# POWER.net
KiCad netlist of a schematic drawn in Altium Designer
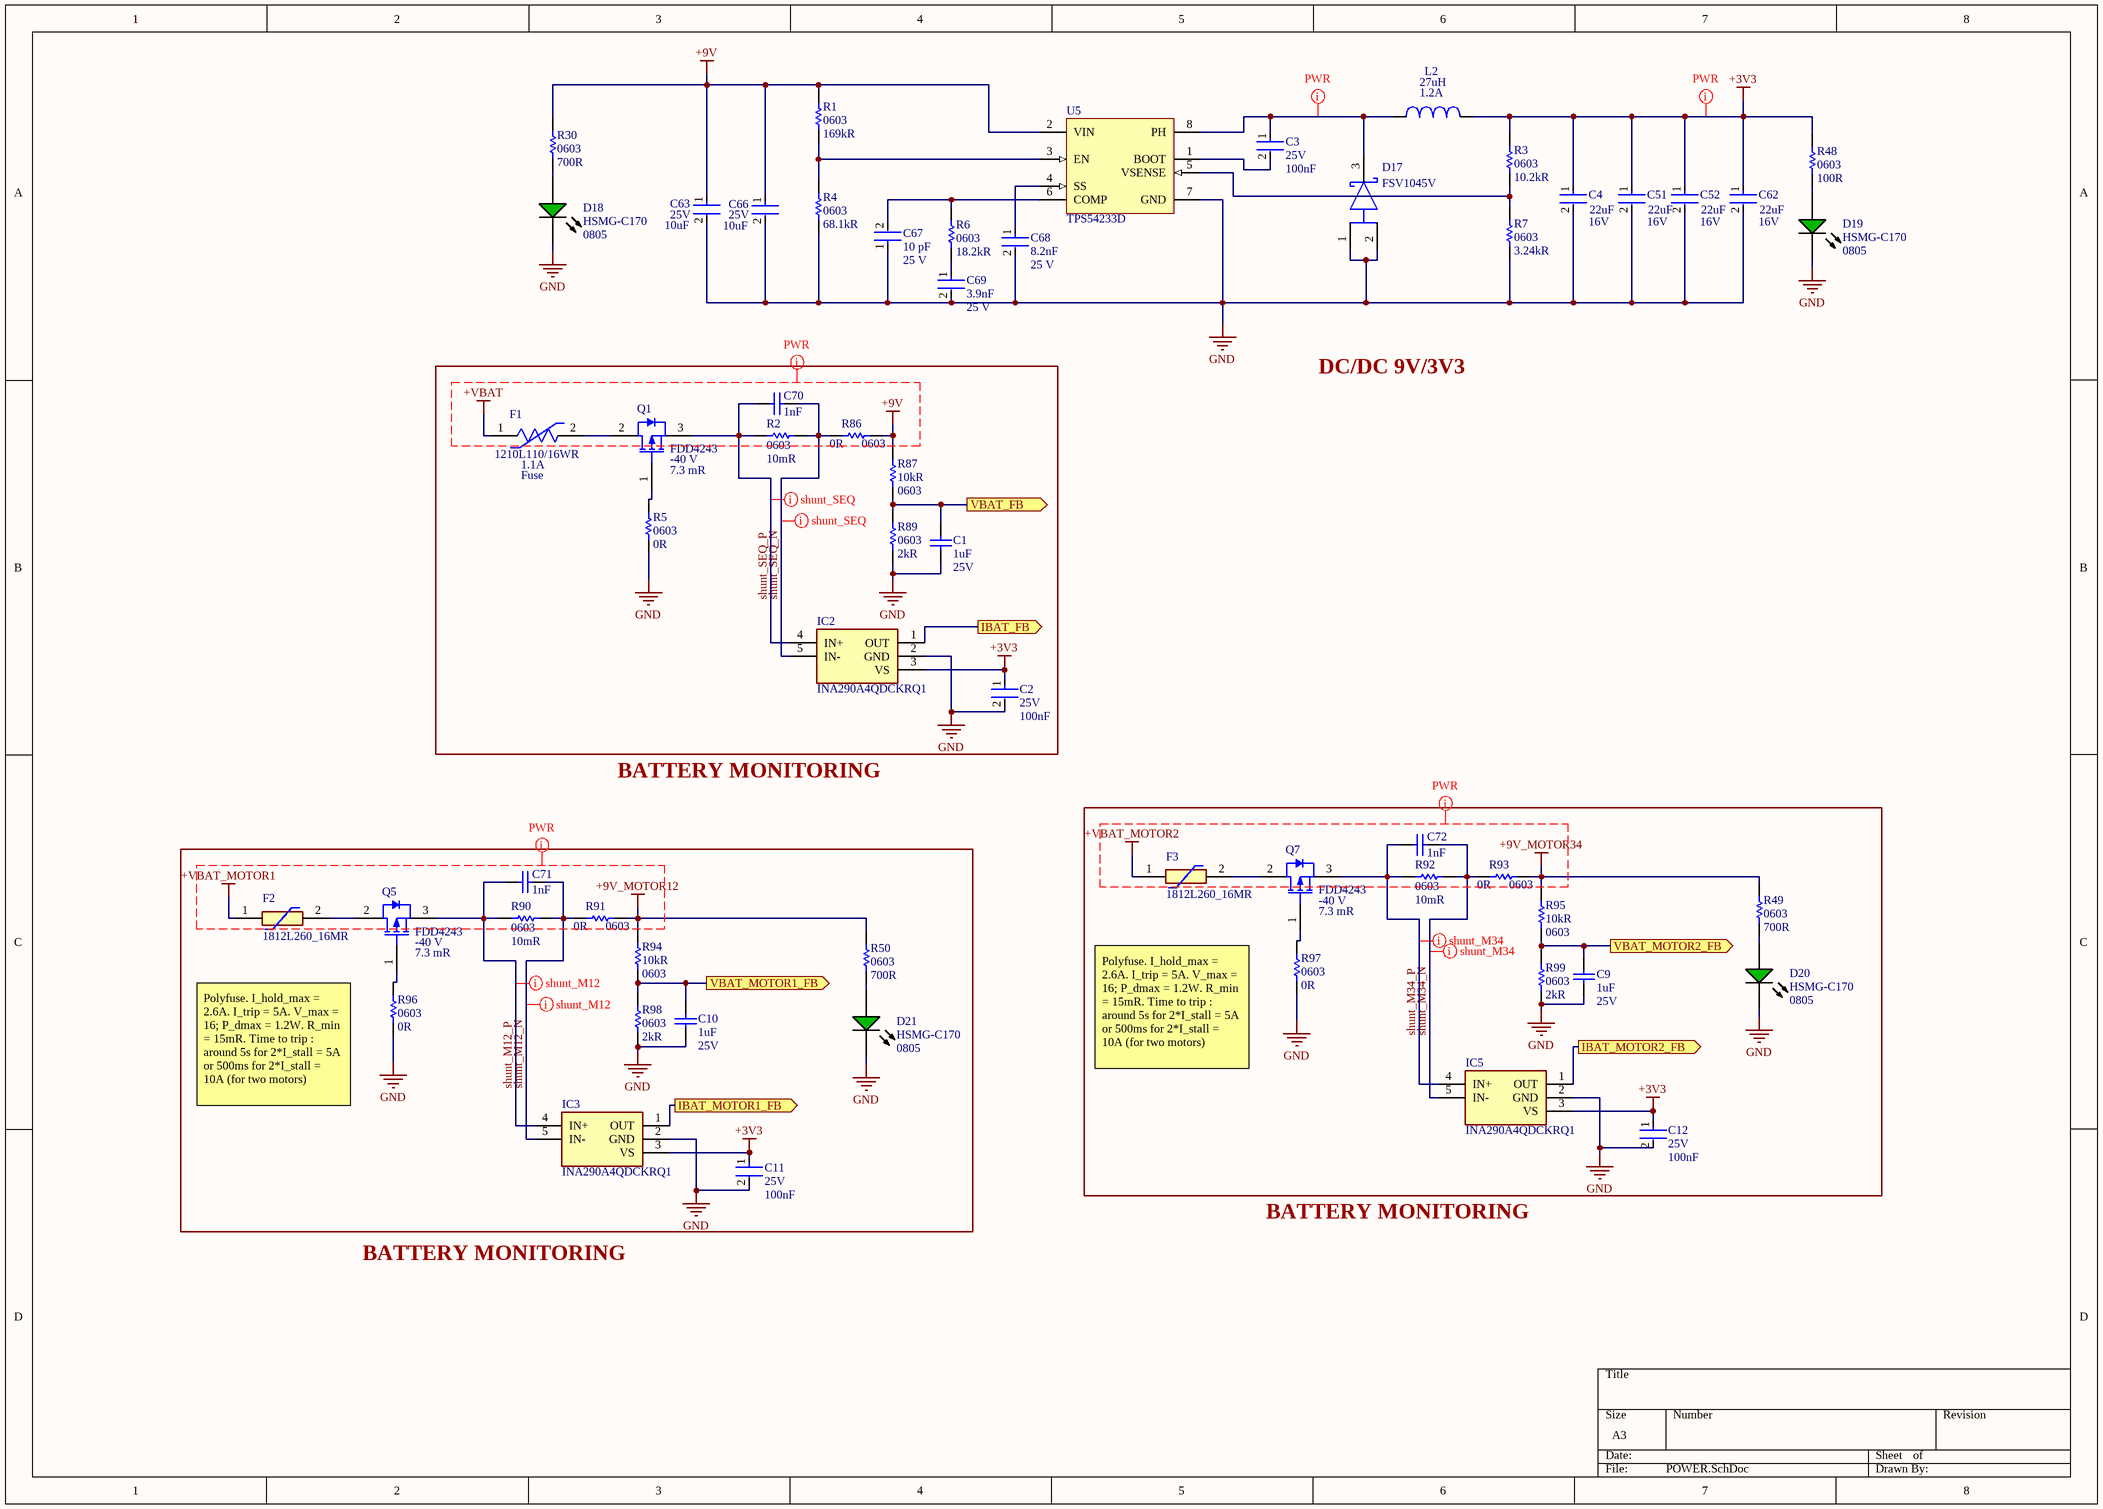
[diagram p0: POWER.SchDoc]

(export (version "E")
  (design (tool "Eeschema 10.0.6"))
  (components
    (comp (ref "C1")
      (value "C0603C105K3PAC7867")
      (footprint "CAPC1608X90X35LL15T15")
      (fields
        (field (name "MANUFACTURER") "Kemet")
        (field (name "MANUFACTURER PART NUMBER") "C0603C105K3PACTU")
        (field (name "CAPACITANCE") "1uF")
        (field (name "TOLERANCE") "10%")
        (field (name "VOLTAGE RATING (DC)") "25V")
      )
      (libsource (lib "Altium Content Vault") (part "CAP"))
    )
    (comp (ref "C2")
      (value "CGA3E2X7R1E104K080AA")
      (footprint "FP-CGA3E-0_3-0_1-MFG")
      (description "Cap Ceramic 100nF 25V X7R 10% Pad SMD 0603 +125°C Automotive T/R")
      (fields
        (field (name "VOLTAGE RATING (DC)") "25V")
        (field (name "CAPACITANCE") "100nF")
        (field (name "TOLERANCE") "10%")
        (field (name "MANUFACTURER") "TDK")
      )
      (libsource (lib "Altium Content Vault") (part "b4654b650e69147ec39a6b967a45e02"))
    )
    (comp (ref "C3")
      (value "CGA3E2X7R1E104K080AA")
      (footprint "FP-CGA3E-0_3-0_1-MFG")
      (description "Cap Ceramic 100nF 25V X7R 10% Pad SMD 0603 +125°C Automotive T/R")
      (fields
        (field (name "VOLTAGE RATING (DC)") "25V")
        (field (name "CAPACITANCE") "100nF")
        (field (name "TOLERANCE") "10%")
        (field (name "MANUFACTURER") "TDK")
      )
      (libsource (lib "Altium Content Vault") (part "b4654b650e69147ec39a6b967a45e02"))
    )
    (comp (ref "C4")
      (value "22uF")
      (footprint "FP-C2012-125-MFG")
      (description "CAP CER 22UF 16V X5R 0805")
      (fields
        (field (name "MANUFACTURER") "TDK")
        (field (name "OCTOPART") "https://octopart.com/c2012x5r1c226k125ac-tdk-25947713")
        (field (name "VOLTAGE") "16V")
      )
      (libsource (lib "Altium Content Vault") (part "11868f565c42a9108669ba33697ecf6"))
    )
    (comp (ref "C9")
      (value "C0603C105K3PAC7867")
      (footprint "CAPC1608X90X35LL15T15")
      (fields
        (field (name "MANUFACTURER") "Kemet")
        (field (name "MANUFACTURER PART NUMBER") "C0603C105K3PACTU")
        (field (name "CAPACITANCE") "1uF")
        (field (name "TOLERANCE") "10%")
        (field (name "VOLTAGE RATING (DC)") "25V")
      )
      (libsource (lib "Altium Content Vault") (part "CAP"))
    )
    (comp (ref "C10")
      (value "C0603C105K3PAC7867")
      (footprint "CAPC1608X90X35LL15T15")
      (fields
        (field (name "MANUFACTURER") "Kemet")
        (field (name "MANUFACTURER PART NUMBER") "C0603C105K3PACTU")
        (field (name "CAPACITANCE") "1uF")
        (field (name "TOLERANCE") "10%")
        (field (name "VOLTAGE RATING (DC)") "25V")
      )
      (libsource (lib "Altium Content Vault") (part "CAP"))
    )
    (comp (ref "C11")
      (value "CGA3E2X7R1E104K080AA")
      (footprint "FP-CGA3E-0_3-0_1-MFG")
      (description "Cap Ceramic 100nF 25V X7R 10% Pad SMD 0603 +125°C Automotive T/R")
      (fields
        (field (name "VOLTAGE RATING (DC)") "25V")
        (field (name "CAPACITANCE") "100nF")
        (field (name "TOLERANCE") "10%")
        (field (name "MANUFACTURER") "TDK")
      )
      (libsource (lib "Altium Content Vault") (part "b4654b650e69147ec39a6b967a45e02"))
    )
    (comp (ref "C12")
      (value "CGA3E2X7R1E104K080AA")
      (footprint "FP-CGA3E-0_3-0_1-MFG")
      (description "Cap Ceramic 100nF 25V X7R 10% Pad SMD 0603 +125°C Automotive T/R")
      (fields
        (field (name "VOLTAGE RATING (DC)") "25V")
        (field (name "CAPACITANCE") "100nF")
        (field (name "TOLERANCE") "10%")
        (field (name "MANUFACTURER") "TDK")
      )
      (libsource (lib "Altium Content Vault") (part "b4654b650e69147ec39a6b967a45e02"))
    )
    (comp (ref "C51")
      (value "22uF")
      (footprint "FP-C2012-125-MFG")
      (description "CAP CER 22UF 16V X5R 0805")
      (fields
        (field (name "MANUFACTURER") "TDK")
        (field (name "OCTOPART") "https://octopart.com/c2012x5r1c226k125ac-tdk-25947713")
        (field (name "VOLTAGE") "16V")
      )
      (libsource (lib "Altium Content Vault") (part "11868f565c42a9108669ba33697ecf6"))
    )
    (comp (ref "C52")
      (value "22uF")
      (footprint "FP-C2012-125-MFG")
      (description "CAP CER 22UF 16V X5R 0805")
      (fields
        (field (name "MANUFACTURER") "TDK")
        (field (name "OCTOPART") "https://octopart.com/c2012x5r1c226k125ac-tdk-25947713")
        (field (name "VOLTAGE") "16V")
      )
      (libsource (lib "Altium Content Vault") (part "11868f565c42a9108669ba33697ecf6"))
    )
    (comp (ref "C62")
      (value "22uF")
      (footprint "FP-C2012-125-MFG")
      (description "CAP CER 22UF 16V X5R 0805")
      (fields
        (field (name "MANUFACTURER") "TDK")
        (field (name "OCTOPART") "https://octopart.com/c2012x5r1c226k125ac-tdk-25947713")
        (field (name "VOLTAGE") "16V")
      )
      (libsource (lib "Altium Content Vault") (part "11868f565c42a9108669ba33697ecf6"))
    )
    (comp (ref "C63")
      (value "C2012X5R1E106K125AB")
      (footprint "FP-C2012-125-0_2-IPC_B")
      (description "Multilayer Ceramic Capacitors 10μF ±10% 25V X5R SMD 0805")
      (fields
        (field (name "VOLTAGE") "25V")
        (field (name "VOLTAGE RATING (DC)") "25V")
        (field (name "TOLERANCE") "10%")
        (field (name "CAPACITANCE") "10uF")
      )
      (libsource (lib "Altium Content Vault") (part "b4654b650e69147ec39a6b967a45e02"))
    )
    (comp (ref "C66")
      (value "C2012X5R1E106K125AB")
      (footprint "FP-C2012-125-0_2-IPC_B")
      (description "Multilayer Ceramic Capacitors 10μF ±10% 25V X5R SMD 0805")
      (fields
        (field (name "VOLTAGE") "25V")
        (field (name "VOLTAGE RATING (DC)") "25V")
        (field (name "TOLERANCE") "10%")
        (field (name "CAPACITANCE") "10uF")
      )
      (libsource (lib "Altium Content Vault") (part "b4654b650e69147ec39a6b967a45e02"))
    )
    (comp (ref "C67")
      (value "C0603C100J3GACTU")
      (footprint "FP-C0603C-CF-MFG")
      (description "CAP CER 10PF 25V NP0 0603")
      (fields
        (field (name "CAPACITANCE") "10 pF")
        (field (name "TOLERANCE") "0.05")
        (field (name "OCTOPART") "https://octopart.com/c0603c100j3gactu-kemet-16430573")
        (field (name "VOLTAGE RATING") "25 V")
      )
      (libsource (lib "Altium Content Vault") (part "b4654b650e69147ec39a6b967a45e02"))
    )
    (comp (ref "C68")
      (value "8.2nF")
      (footprint "FP-C0603C-CF-MFG")
      (description "CAP CER 8200PF 25V X7R 0603")
      (fields
        (field (name "MANUFACTURER") "KEMET")
        (field (name "OCTOPART") "https://octopart.com/c0603c822k3ractu-kemet-9144236")
        (field (name "VOLTAGE RATING") "25 V")
      )
      (libsource (lib "Altium Content Vault") (part "b4654b650e69147ec39a6b967a45e02"))
    )
    (comp (ref "C69")
      (value "C0603C392K3RACTU")
      (footprint "FP-C0603C-CF-MFG")
      (description "CAP CER 3900PF 25V X7R 0603")
      (fields
        (field (name "CAPACITANCE") "3.9nF")
        (field (name "OCTOPART") "https://octopart.com/c0603c392k3ractu-kemet-12624904")
        (field (name "TOLERANCE") "0.1")
        (field (name "VOLTAGE RATING") "25 V")
      )
      (libsource (lib "Altium Content Vault") (part "b4654b650e69147ec39a6b967a45e02"))
    )
    (comp (ref "C70")
      (value "1nF")
      (footprint "SAMS-C0603-2_M")
      (description "Multi-layer Ceramic Capacitor, -55 to 125 degC, 2-Pin SMD (0603), RoHS, Tape and Reel")
      (fields (field (name "MANUFACTURER") "Samsung Electro-Mechanics"))
      (libsource (lib "Altium Content Vault") (part "CAP-NP-2"))
    )
    (comp (ref "C71")
      (value "1nF")
      (footprint "SAMS-C0603-2_M")
      (description "Multi-layer Ceramic Capacitor, -55 to 125 degC, 2-Pin SMD (0603), RoHS, Tape and Reel")
      (fields (field (name "MANUFACTURER") "Samsung Electro-Mechanics"))
      (libsource (lib "Altium Content Vault") (part "CAP-NP-2"))
    )
    (comp (ref "C72")
      (value "1nF")
      (footprint "SAMS-C0603-2_M")
      (description "Multi-layer Ceramic Capacitor, -55 to 125 degC, 2-Pin SMD (0603), RoHS, Tape and Reel")
      (fields (field (name "MANUFACTURER") "Samsung Electro-Mechanics"))
      (libsource (lib "Altium Content Vault") (part "CAP-NP-2"))
    )
    (comp (ref "D17")
      (value "FSV1045V")
      (footprint "FP-340BQ-MFG")
      (description "DIODE SCHOTTKY 45V 10A TO277-3")
      (fields
        (field (name "MANUFACTURER") "ON Semiconductor")
        (field (name "OCTOPART") "https://octopart.com/fsv1045v-on+semiconductor-84328650")
      )
      (libsource (lib "Altium Content Vault") (part "da46661e6711e9042e243bb90b6b5f6"))
    )
    (comp (ref "D18")
      (value "HSMG-C170")
      (footprint "AVAG-HSMX-C170_V")
      (description "Chip LED, Green, 2.2 V, -40 to 85 degC, 2-Pin SMD, Pb-Free, Tape and Reel")
      (fields (field (name "MANUFACTURER") "Avago") (field (name "CASE/PACKAGE") "0805"))
      (libsource (lib "Altium Content Vault") (part "LED_GREEN_A1K2-2"))
    )
    (comp (ref "D19")
      (value "HSMG-C170")
      (footprint "AVAG-HSMX-C170_V")
      (description "Chip LED, Green, 2.2 V, -40 to 85 degC, 2-Pin SMD, Pb-Free, Tape and Reel")
      (fields (field (name "MANUFACTURER") "Avago") (field (name "CASE/PACKAGE") "0805"))
      (libsource (lib "Altium Content Vault") (part "LED_GREEN_A1K2-2"))
    )
    (comp (ref "D20")
      (value "HSMG-C170")
      (footprint "AVAG-HSMX-C170_V")
      (description "Chip LED, Green, 2.2 V, -40 to 85 degC, 2-Pin SMD, Pb-Free, Tape and Reel")
      (fields (field (name "MANUFACTURER") "Avago") (field (name "CASE/PACKAGE") "0805"))
      (libsource (lib "Altium Content Vault") (part "LED_GREEN_A1K2-2"))
    )
    (comp (ref "D21")
      (value "HSMG-C170")
      (footprint "AVAG-HSMX-C170_V")
      (description "Chip LED, Green, 2.2 V, -40 to 85 degC, 2-Pin SMD, Pb-Free, Tape and Reel")
      (fields (field (name "MANUFACTURER") "Avago") (field (name "CASE/PACKAGE") "0805"))
      (libsource (lib "Altium Content Vault") (part "LED_GREEN_A1K2-2"))
    )
    (comp (ref "F1")
      (value "1210L110/16WR")
      (footprint "FP-1210L110-16WR-MFG")
      (description "PTC RESET FUSE 16V 1.1A 1210")
      (fields
        (field (name "HOLD CURRENT") "1.1A")
        (field (name "CATEGORY") "Fuse")
        (field (name "OCTOPART") "https://octopart.com/1210l110%2F16wr-littelfuse-28867107")
        (field (name "MANUFACTURER") "Littelfuse Inc")
      )
      (libsource (lib "Altium Content Vault") (part "1c6d77a0208143737455a0c7eb396be"))
    )
    (comp (ref "F2")
      (value "1812L260_16MR")
      (footprint "SamacSys:1812L010DR")
      (description "Resettable Fuse")
      (fields
        (field (name "MANUFACTURER_PART_NUMBER") "1812L260/16MR")
        (field (name "MOUSER PART NUMBER") "576-1812L260/16MR")
      )
      (libsource (lib "*") (part "1812L260_16MR"))
    )
    (comp (ref "F3")
      (value "1812L260_16MR")
      (footprint "SamacSys:1812L010DR")
      (description "Resettable Fuse")
      (fields
        (field (name "MANUFACTURER_PART_NUMBER") "1812L260/16MR")
        (field (name "MOUSER PART NUMBER") "576-1812L260/16MR")
      )
      (libsource (lib "*") (part "1812L260_16MR"))
    )
    (comp (ref "IC2")
      (value "INA290A4QDCKRQ1")
      (footprint "SamacSys:SOT65P210X110-5N")
      (description "Integrated Circuit")
      (fields (field (name "MOUSER PART NUMBER") "595-INA290A4QDCKRQ1"))
      (libsource (lib "*") (part "INA290A4QDCKRQ1"))
    )
    (comp (ref "IC3")
      (value "INA290A4QDCKRQ1")
      (footprint "SamacSys:SOT65P210X110-5N")
      (description "Integrated Circuit")
      (fields (field (name "MOUSER PART NUMBER") "595-INA290A4QDCKRQ1"))
      (libsource (lib "*") (part "INA290A4QDCKRQ1"))
    )
    (comp (ref "IC5")
      (value "INA290A4QDCKRQ1")
      (footprint "SamacSys:SOT65P210X110-5N")
      (description "Integrated Circuit")
      (fields (field (name "MOUSER PART NUMBER") "595-INA290A4QDCKRQ1"))
      (libsource (lib "*") (part "INA290A4QDCKRQ1"))
    )
    (comp (ref "L2")
      (value "SRR6038-270Y")
      (footprint "SRR6038-3R3Y:SRR6038")
      (description "Inductor Power Shielded Wirewound 27uH 30% 100KHz 7.7Q-Factor Ferrite 1.2A 0.109Ohm DCR T/R")
      (fields
        (field (name "MANUFACTURER") "Bourns")
        (field (name "TOLERANCE") "30%")
        (field (name "INDUCTANCE") "27uH")
        (field (name "MAX DC CURRENT") "1.2A")
      )
      (libsource (lib "*") (part "SRR6038-3R3Y"))
    )
    (comp (ref "Q1")
      (value "FDD4243")
      (footprint "INF-PG-TO252-3-313_L")
      (description "OptiMOS-P2 Power-Transistor, -40 V VDS, -85 A ID, PG-TO252-3-313, Reel, Green")
      (fields
        (field (name "PARTNUMBER") "IPD85P04P4-07")
        (field (name "VDS (MAX)") "-40 V")
        (field (name "RDS (ON) (MAX) (@10V)") "7.3 mR")
        (field (name "MANUFACTURER") "Infineon")
      )
      (libsource (lib "Altium Content Vault") (part "INF-MOSFET-P-3"))
    )
    (comp (ref "Q5")
      (value "FDD4243")
      (footprint "INF-PG-TO252-3-313_L")
      (description "OptiMOS-P2 Power-Transistor, -40 V VDS, -85 A ID, PG-TO252-3-313, Reel, Green")
      (fields
        (field (name "PARTNUMBER") "IPD85P04P4-07")
        (field (name "VDS (MAX)") "-40 V")
        (field (name "RDS (ON) (MAX) (@10V)") "7.3 mR")
        (field (name "MANUFACTURER") "Infineon")
      )
      (libsource (lib "Altium Content Vault") (part "INF-MOSFET-P-3"))
    )
    (comp (ref "Q7")
      (value "FDD4243")
      (footprint "INF-PG-TO252-3-313_L")
      (description "OptiMOS-P2 Power-Transistor, -40 V VDS, -85 A ID, PG-TO252-3-313, Reel, Green")
      (fields
        (field (name "PARTNUMBER") "IPD85P04P4-07")
        (field (name "VDS (MAX)") "-40 V")
        (field (name "RDS (ON) (MAX) (@10V)") "7.3 mR")
        (field (name "MANUFACTURER") "Infineon")
      )
      (libsource (lib "Altium Content Vault") (part "INF-MOSFET-P-3"))
    )
    (comp (ref "R1")
      (value "ERJ-3EKF1693V")
      (footprint "RESC1608X55X30ML15T15")
      (fields
        (field (name "MANUFACTURER") "Panasonic")
        (field (name "CASE CODE (IMPERIAL)") "0603")
        (field (name "TOLERANCE") "1%")
        (field (name "RESISTANCE") "169kR")
      )
      (libsource (lib "Altium Content Vault") (part "RES"))
    )
    (comp (ref "R2")
      (value "WSL0603R0100FEA")
      (footprint "RESC1508X46X38ML25T25")
      (fields
        (field (name "MANUFACTURER") "Vishay Dale")
        (field (name "CASE CODE (IMPERIAL)") "0603")
        (field (name "TOLERANCE") "1%")
        (field (name "RESISTANCE") "10mR")
      )
      (libsource (lib "Altium Content Vault") (part "RES"))
    )
    (comp (ref "R3")
      (value "ERJ-3EKF1022V")
      (footprint "RESC1608X55X30LL15T15")
      (fields
        (field (name "MANUFACTURER") "Panasonic")
        (field (name "CASE CODE (IMPERIAL)") "0603")
        (field (name "RESISTANCE") "10.2kR")
        (field (name "TOLERANCE") "1%")
      )
      (libsource (lib "Altium Content Vault") (part "RES"))
    )
    (comp (ref "R4")
      (value "ERJ-3EKF6812V")
      (footprint "RESC1608X55X30ML15T15")
      (fields
        (field (name "MANUFACTURER") "Panasonic")
        (field (name "CASE CODE (IMPERIAL)") "0603")
        (field (name "RESISTANCE") "68.1kR")
        (field (name "TOLERANCE") "1%")
      )
      (libsource (lib "Altium Content Vault") (part "RES"))
    )
    (comp (ref "R5")
      (value "RC0603JR-070RL")
      (footprint "RESC1608X55X25ML10T15")
      (description "Chip Resistor, 0 Ohm, +/- 5%, 0.1 W, -55 to 155 degC, 0603 (1608 Metric), RoHS, Tape and Reel")
      (fields
        (field (name "TOLERANCE") "5%")
        (field (name "CASE CODE (IMPERIAL)") "0603")
        (field (name "RESISTANCE") "0R")
        (field (name "MANUFACTURER") "Yageo")
      )
      (libsource (lib "Altium Content Vault") (part "RES-2"))
    )
    (comp (ref "R6")
      (value "ERJ-3EKF1822V")
      (footprint "RESC1608X55X30NL15T15")
      (fields
        (field (name "MANUFACTURER") "Panasonic")
        (field (name "MANUFACTURER PART NUMBER") "ERJ3EKF1822V")
        (field (name "CASE CODE (IMPERIAL)") "0603")
        (field (name "RESISTANCE") "18.2kR")
        (field (name "TOLERANCE") "1%")
      )
      (libsource (lib "Altium Content Vault") (part "RES"))
    )
    (comp (ref "R7")
      (value "ERJ-3EKF3241V")
      (footprint "RESC1608X55X30ML15T15")
      (fields
        (field (name "MANUFACTURER") "Panasonic")
        (field (name "CASE CODE (IMPERIAL)") "0603")
        (field (name "RESISTANCE") "3.24kR")
        (field (name "TOLERANCE") "1%")
      )
      (libsource (lib "Altium Content Vault") (part "RES"))
    )
    (comp (ref "R30")
      (value "CRCW060390R9FKEA")
      (footprint "RESC1609X50X30NL10T20")
      (fields
        (field (name "MANUFACTURER") "Vishay Dale")
        (field (name "CASE CODE (IMPERIAL)") "0603")
        (field (name "RESISTANCE") "700R")
        (field (name "TOLERANCE") "1%")
      )
      (libsource (lib "Altium Content Vault") (part "RES"))
    )
    (comp (ref "R48")
      (value "CRCW060390R9FKEA")
      (footprint "RESC1609X50X30NL10T20")
      (fields
        (field (name "MANUFACTURER") "Vishay Dale")
        (field (name "CASE CODE (IMPERIAL)") "0603")
        (field (name "RESISTANCE") "100R")
        (field (name "TOLERANCE") "1%")
      )
      (libsource (lib "Altium Content Vault") (part "RES"))
    )
    (comp (ref "R49")
      (value "CRCW060390R9FKEA")
      (footprint "RESC1609X50X30NL10T20")
      (fields
        (field (name "MANUFACTURER") "Vishay Dale")
        (field (name "CASE CODE (IMPERIAL)") "0603")
        (field (name "RESISTANCE") "700R")
        (field (name "TOLERANCE") "1%")
      )
      (libsource (lib "Altium Content Vault") (part "RES"))
    )
    (comp (ref "R50")
      (value "CRCW060390R9FKEA")
      (footprint "RESC1609X50X30NL10T20")
      (fields
        (field (name "MANUFACTURER") "Vishay Dale")
        (field (name "CASE CODE (IMPERIAL)") "0603")
        (field (name "RESISTANCE") "700R")
        (field (name "TOLERANCE") "1%")
      )
      (libsource (lib "Altium Content Vault") (part "RES"))
    )
    (comp (ref "R86")
      (value "RC0603JR-070RL")
      (footprint "RESC1608X55X25ML10T15")
      (description "Chip Resistor, 0 Ohm, +/- 5%, 0.1 W, -55 to 155 degC, 0603 (1608 Metric), RoHS, Tape and Reel")
      (fields
        (field (name "TOLERANCE") "5%")
        (field (name "CASE CODE (IMPERIAL)") "0603")
        (field (name "RESISTANCE") "0R")
        (field (name "MANUFACTURER") "Yageo")
      )
      (libsource (lib "Altium Content Vault") (part "RES-2"))
    )
    (comp (ref "R87")
      (value "ERJ3EKF1002V")
      (footprint "RESC1609X55X30LL15T15")
      (description "Chip Resistor, 10 KOhm, +/- 1%, 0.1 W, -55 to 155 degC, 0603 (1608 Metric), RoHS, Tape and Reel")
      (fields
        (field (name "RESISTANCE") "10kR")
        (field (name "CASE CODE (IMPERIAL)") "0603")
        (field (name "TOLERANCE") "1%")
        (field (name "MANUFACTURER") "Panasonic")
      )
      (libsource (lib "Altium Content Vault") (part "RES-2"))
    )
    (comp (ref "R89")
      (value "ERJ-3EKF2001V")
      (footprint "RESC1608X55X30ML15T15")
      (fields
        (field (name "MANUFACTURER") "Panasonic")
        (field (name "CASE CODE (IMPERIAL)") "0603")
        (field (name "RESISTANCE") "2kR")
        (field (name "TOLERANCE") "1%")
      )
      (libsource (lib "Altium Content Vault") (part "RES"))
    )
    (comp (ref "R90")
      (value "WSL0603R0100FEA")
      (footprint "RESC1508X46X38ML25T25")
      (fields
        (field (name "MANUFACTURER") "Vishay Dale")
        (field (name "CASE CODE (IMPERIAL)") "0603")
        (field (name "TOLERANCE") "1%")
        (field (name "RESISTANCE") "10mR")
      )
      (libsource (lib "Altium Content Vault") (part "RES"))
    )
    (comp (ref "R91")
      (value "RC0603JR-070RL")
      (footprint "RESC1608X55X25ML10T15")
      (description "Chip Resistor, 0 Ohm, +/- 5%, 0.1 W, -55 to 155 degC, 0603 (1608 Metric), RoHS, Tape and Reel")
      (fields
        (field (name "TOLERANCE") "5%")
        (field (name "CASE CODE (IMPERIAL)") "0603")
        (field (name "RESISTANCE") "0R")
        (field (name "MANUFACTURER") "Yageo")
      )
      (libsource (lib "Altium Content Vault") (part "RES-2"))
    )
    (comp (ref "R92")
      (value "WSL0603R0100FEA")
      (footprint "RESC1508X46X38ML25T25")
      (fields
        (field (name "MANUFACTURER") "Vishay Dale")
        (field (name "CASE CODE (IMPERIAL)") "0603")
        (field (name "TOLERANCE") "1%")
        (field (name "RESISTANCE") "10mR")
      )
      (libsource (lib "Altium Content Vault") (part "RES"))
    )
    (comp (ref "R93")
      (value "RC0603JR-070RL")
      (footprint "RESC1608X55X25ML10T15")
      (description "Chip Resistor, 0 Ohm, +/- 5%, 0.1 W, -55 to 155 degC, 0603 (1608 Metric), RoHS, Tape and Reel")
      (fields
        (field (name "TOLERANCE") "5%")
        (field (name "CASE CODE (IMPERIAL)") "0603")
        (field (name "RESISTANCE") "0R")
        (field (name "MANUFACTURER") "Yageo")
      )
      (libsource (lib "Altium Content Vault") (part "RES-2"))
    )
    (comp (ref "R94")
      (value "ERJ3EKF1002V")
      (footprint "RESC1609X55X30LL15T15")
      (description "Chip Resistor, 10 KOhm, +/- 1%, 0.1 W, -55 to 155 degC, 0603 (1608 Metric), RoHS, Tape and Reel")
      (fields
        (field (name "RESISTANCE") "10kR")
        (field (name "CASE CODE (IMPERIAL)") "0603")
        (field (name "TOLERANCE") "1%")
        (field (name "MANUFACTURER") "Panasonic")
      )
      (libsource (lib "Altium Content Vault") (part "RES-2"))
    )
    (comp (ref "R95")
      (value "ERJ3EKF1002V")
      (footprint "RESC1609X55X30LL15T15")
      (description "Chip Resistor, 10 KOhm, +/- 1%, 0.1 W, -55 to 155 degC, 0603 (1608 Metric), RoHS, Tape and Reel")
      (fields
        (field (name "RESISTANCE") "10kR")
        (field (name "CASE CODE (IMPERIAL)") "0603")
        (field (name "TOLERANCE") "1%")
        (field (name "MANUFACTURER") "Panasonic")
      )
      (libsource (lib "Altium Content Vault") (part "RES-2"))
    )
    (comp (ref "R96")
      (value "RC0603JR-070RL")
      (footprint "RESC1608X55X25ML10T15")
      (description "Chip Resistor, 0 Ohm, +/- 5%, 0.1 W, -55 to 155 degC, 0603 (1608 Metric), RoHS, Tape and Reel")
      (fields
        (field (name "TOLERANCE") "5%")
        (field (name "CASE CODE (IMPERIAL)") "0603")
        (field (name "RESISTANCE") "0R")
        (field (name "MANUFACTURER") "Yageo")
      )
      (libsource (lib "Altium Content Vault") (part "RES-2"))
    )
    (comp (ref "R97")
      (value "RC0603JR-070RL")
      (footprint "RESC1608X55X25ML10T15")
      (description "Chip Resistor, 0 Ohm, +/- 5%, 0.1 W, -55 to 155 degC, 0603 (1608 Metric), RoHS, Tape and Reel")
      (fields
        (field (name "TOLERANCE") "5%")
        (field (name "CASE CODE (IMPERIAL)") "0603")
        (field (name "RESISTANCE") "0R")
        (field (name "MANUFACTURER") "Yageo")
      )
      (libsource (lib "Altium Content Vault") (part "RES-2"))
    )
    (comp (ref "R98")
      (value "ERJ-3EKF2001V")
      (footprint "RESC1608X55X30ML15T15")
      (fields
        (field (name "MANUFACTURER") "Panasonic")
        (field (name "CASE CODE (IMPERIAL)") "0603")
        (field (name "RESISTANCE") "2kR")
        (field (name "TOLERANCE") "1%")
      )
      (libsource (lib "Altium Content Vault") (part "RES"))
    )
    (comp (ref "R99")
      (value "ERJ-3EKF2001V")
      (footprint "RESC1608X55X30ML15T15")
      (fields
        (field (name "MANUFACTURER") "Panasonic")
        (field (name "CASE CODE (IMPERIAL)") "0603")
        (field (name "RESISTANCE") "2kR")
        (field (name "TOLERANCE") "1%")
      )
      (libsource (lib "Altium Content Vault") (part "RES"))
    )
    (comp (ref "U5")
      (value "TPS54233D")
      (footprint "D0008A_M")
      (fields (field (name "MANUFACTURER") "Texas Instruments"))
      (libsource (lib "Altium Content Vault") (part "TI-TPS54233D8"))
    )
  )
  (nets
    (net (code "1") (name "+3V3") (class "Default")
      (node (ref "C11") (pin "1") (pinfunction "1_1") (pintype "passive"))
      (node (ref "C12") (pin "1") (pinfunction "1_1") (pintype "passive"))
      (node (ref "C2") (pin "1") (pinfunction "1_1") (pintype "passive"))
      (node (ref "C4") (pin "1") (pinfunction "1_1") (pintype "passive"))
      (node (ref "C51") (pin "1") (pinfunction "1_1") (pintype "passive"))
      (node (ref "C52") (pin "1") (pinfunction "1_1") (pintype "passive"))
      (node (ref "C62") (pin "1") (pinfunction "1_1") (pintype "passive"))
      (node (ref "IC2") (pin "3") (pinfunction "VS_3") (pintype "passive"))
      (node (ref "IC3") (pin "3") (pinfunction "VS_3") (pintype "passive"))
      (node (ref "IC5") (pin "3") (pinfunction "VS_3") (pintype "passive"))
      (node (ref "L2") (pin "2") (pinfunction "2_2") (pintype "passive"))
      (node (ref "R3") (pin "2") (pinfunction "2_2") (pintype "passive"))
      (node (ref "R48") (pin "2") (pinfunction "2_2") (pintype "passive"))
    )
    (net (code "2") (name "+9V") (class "Default")
      (node (ref "C63") (pin "1") (pinfunction "1_1") (pintype "passive"))
      (node (ref "C66") (pin "1") (pinfunction "1_1") (pintype "passive"))
      (node (ref "R1") (pin "2") (pinfunction "2_2") (pintype "passive"))
      (node (ref "R30") (pin "2") (pinfunction "2_2") (pintype "passive"))
      (node (ref "R86") (pin "2") (pinfunction "2_2") (pintype "passive"))
      (node (ref "R87") (pin "2") (pinfunction "2_2") (pintype "passive"))
      (node (ref "U5") (pin "2") (pinfunction "VIN_2") (pintype "power_in"))
    )
    (net (code "3") (name "+9V_MOTOR12") (class "Default")
      (node (ref "R50") (pin "2") (pinfunction "2_2") (pintype "passive"))
      (node (ref "R91") (pin "2") (pinfunction "2_2") (pintype "passive"))
      (node (ref "R94") (pin "2") (pinfunction "2_2") (pintype "passive"))
    )
    (net (code "4") (name "+9V_MOTOR34") (class "Default")
      (node (ref "R49") (pin "2") (pinfunction "2_2") (pintype "passive"))
      (node (ref "R93") (pin "2") (pinfunction "2_2") (pintype "passive"))
      (node (ref "R95") (pin "2") (pinfunction "2_2") (pintype "passive"))
    )
    (net (code "5") (name "+VBAT") (class "Default")
      (node (ref "F1") (pin "1") (pinfunction "1_1") (pintype "passive"))
    )
    (net (code "6") (name "+VBAT_MOTOR1") (class "Default")
      (node (ref "F2") (pin "1") (pinfunction "1_1") (pintype "passive"))
    )
    (net (code "7") (name "+VBAT_MOTOR2") (class "Default")
      (node (ref "F3") (pin "1") (pinfunction "1_1") (pintype "passive"))
    )
    (net (code "8") (name "/IBAT_FB") (class "Default")
      (node (ref "IC2") (pin "1") (pinfunction "OUT_1") (pintype "passive"))
    )
    (net (code "9") (name "/IBAT_MOTOR1_FB") (class "Default")
      (node (ref "IC3") (pin "1") (pinfunction "OUT_1") (pintype "passive"))
    )
    (net (code "10") (name "/IBAT_MOTOR2_FB") (class "Default")
      (node (ref "IC5") (pin "1") (pinfunction "OUT_1") (pintype "passive"))
    )
    (net (code "11") (name "/VBAT_FB") (class "Default")
      (node (ref "C1") (pin "2") (pinfunction "2_2") (pintype "passive"))
      (node (ref "R87") (pin "1") (pinfunction "1_1") (pintype "passive"))
      (node (ref "R89") (pin "2") (pinfunction "2_2") (pintype "passive"))
    )
    (net (code "12") (name "/VBAT_MOTOR1_FB") (class "Default")
      (node (ref "C10") (pin "2") (pinfunction "2_2") (pintype "passive"))
      (node (ref "R94") (pin "1") (pinfunction "1_1") (pintype "passive"))
      (node (ref "R98") (pin "2") (pinfunction "2_2") (pintype "passive"))
    )
    (net (code "13") (name "/VBAT_MOTOR2_FB") (class "Default")
      (node (ref "C9") (pin "2") (pinfunction "2_2") (pintype "passive"))
      (node (ref "R95") (pin "1") (pinfunction "1_1") (pintype "passive"))
      (node (ref "R99") (pin "2") (pinfunction "2_2") (pintype "passive"))
    )
    (net (code "14") (name "/shunt_M12_N") (class "Default")
      (node (ref "C71") (pin "1") (pinfunction "1_1") (pintype "passive"))
      (node (ref "IC3") (pin "5") (pinfunction "IN-_5") (pintype "passive"))
      (node (ref "R90") (pin "2") (pinfunction "2_2") (pintype "passive"))
      (node (ref "R91") (pin "1") (pinfunction "1_1") (pintype "passive"))
    )
    (net (code "15") (name "/shunt_M12_P") (class "Default")
      (node (ref "C71") (pin "2") (pinfunction "2_2") (pintype "passive"))
      (node (ref "IC3") (pin "4") (pinfunction "IN+_4") (pintype "passive"))
      (node (ref "Q5") (pin "3") (pinfunction "SOURCE_3") (pintype "passive"))
      (node (ref "R90") (pin "1") (pinfunction "1_1") (pintype "passive"))
    )
    (net (code "16") (name "/shunt_M34_N") (class "Default")
      (node (ref "C72") (pin "1") (pinfunction "1_1") (pintype "passive"))
      (node (ref "IC5") (pin "5") (pinfunction "IN-_5") (pintype "passive"))
      (node (ref "R92") (pin "2") (pinfunction "2_2") (pintype "passive"))
      (node (ref "R93") (pin "1") (pinfunction "1_1") (pintype "passive"))
    )
    (net (code "17") (name "/shunt_M34_P") (class "Default")
      (node (ref "C72") (pin "2") (pinfunction "2_2") (pintype "passive"))
      (node (ref "IC5") (pin "4") (pinfunction "IN+_4") (pintype "passive"))
      (node (ref "Q7") (pin "3") (pinfunction "SOURCE_3") (pintype "passive"))
      (node (ref "R92") (pin "1") (pinfunction "1_1") (pintype "passive"))
    )
    (net (code "18") (name "/shunt_SEQ_N") (class "Default")
      (node (ref "C70") (pin "1") (pinfunction "1_1") (pintype "passive"))
      (node (ref "IC2") (pin "5") (pinfunction "IN-_5") (pintype "passive"))
      (node (ref "R2") (pin "2") (pinfunction "2_2") (pintype "passive"))
      (node (ref "R86") (pin "1") (pinfunction "1_1") (pintype "passive"))
    )
    (net (code "19") (name "/shunt_SEQ_P") (class "Default")
      (node (ref "C70") (pin "2") (pinfunction "2_2") (pintype "passive"))
      (node (ref "IC2") (pin "4") (pinfunction "IN+_4") (pintype "passive"))
      (node (ref "Q1") (pin "3") (pinfunction "SOURCE_3") (pintype "passive"))
      (node (ref "R2") (pin "1") (pinfunction "1_1") (pintype "passive"))
    )
    (net (code "20") (name "GND") (class "Default")
      (node (ref "C1") (pin "1") (pinfunction "1_1") (pintype "passive"))
      (node (ref "C10") (pin "1") (pinfunction "1_1") (pintype "passive"))
      (node (ref "C11") (pin "2") (pinfunction "2_2") (pintype "passive"))
      (node (ref "C12") (pin "2") (pinfunction "2_2") (pintype "passive"))
      (node (ref "C2") (pin "2") (pinfunction "2_2") (pintype "passive"))
      (node (ref "C4") (pin "2") (pinfunction "2_2") (pintype "passive"))
      (node (ref "C51") (pin "2") (pinfunction "2_2") (pintype "passive"))
      (node (ref "C52") (pin "2") (pinfunction "2_2") (pintype "passive"))
      (node (ref "C62") (pin "2") (pinfunction "2_2") (pintype "passive"))
      (node (ref "C63") (pin "2") (pinfunction "2_2") (pintype "passive"))
      (node (ref "C66") (pin "2") (pinfunction "2_2") (pintype "passive"))
      (node (ref "C67") (pin "1") (pinfunction "1_1") (pintype "passive"))
      (node (ref "C68") (pin "2") (pinfunction "2_2") (pintype "passive"))
      (node (ref "C69") (pin "2") (pinfunction "2_2") (pintype "passive"))
      (node (ref "C9") (pin "1") (pinfunction "1_1") (pintype "passive"))
      (node (ref "D17") (pin "1") (pinfunction "A_1") (pintype "passive"))
      (node (ref "D17") (pin "2") (pinfunction "A_2") (pintype "passive"))
      (node (ref "D18") (pin "2") (pinfunction "K_2") (pintype "passive"))
      (node (ref "D19") (pin "2") (pinfunction "K_2") (pintype "passive"))
      (node (ref "D20") (pin "2") (pinfunction "K_2") (pintype "passive"))
      (node (ref "D21") (pin "2") (pinfunction "K_2") (pintype "passive"))
      (node (ref "IC2") (pin "2") (pinfunction "GND_2") (pintype "passive"))
      (node (ref "IC3") (pin "2") (pinfunction "GND_2") (pintype "passive"))
      (node (ref "IC5") (pin "2") (pinfunction "GND_2") (pintype "passive"))
      (node (ref "R4") (pin "1") (pinfunction "1_1") (pintype "passive"))
      (node (ref "R5") (pin "1") (pinfunction "1_1") (pintype "passive"))
      (node (ref "R7") (pin "1") (pinfunction "1_1") (pintype "passive"))
      (node (ref "R89") (pin "1") (pinfunction "1_1") (pintype "passive"))
      (node (ref "R96") (pin "1") (pinfunction "1_1") (pintype "passive"))
      (node (ref "R97") (pin "1") (pinfunction "1_1") (pintype "passive"))
      (node (ref "R98") (pin "1") (pinfunction "1_1") (pintype "passive"))
      (node (ref "R99") (pin "1") (pinfunction "1_1") (pintype "passive"))
      (node (ref "U5") (pin "7") (pinfunction "GND_7") (pintype "power_in"))
    )
    (net (code "21") (name "Net-(C69-Pad1)") (class "Default")
      (node (ref "C69") (pin "1") (pinfunction "1_1") (pintype "passive"))
      (node (ref "R6") (pin "1") (pinfunction "1_1") (pintype "passive"))
    )
    (net (code "22") (name "Net-(D17-C)") (class "Default")
      (node (ref "C3") (pin "1") (pinfunction "1_1") (pintype "passive"))
      (node (ref "D17") (pin "3") (pinfunction "C_3") (pintype "passive"))
      (node (ref "L2") (pin "1") (pinfunction "1_1") (pintype "passive"))
      (node (ref "U5") (pin "8") (pinfunction "PH_8") (pintype "power_in"))
    )
    (net (code "23") (name "Net-(D18-A)") (class "Default")
      (node (ref "D18") (pin "1") (pinfunction "A_1") (pintype "passive"))
      (node (ref "R30") (pin "1") (pinfunction "1_1") (pintype "passive"))
    )
    (net (code "24") (name "Net-(D19-A)") (class "Default")
      (node (ref "D19") (pin "1") (pinfunction "A_1") (pintype "passive"))
      (node (ref "R48") (pin "1") (pinfunction "1_1") (pintype "passive"))
    )
    (net (code "25") (name "Net-(D20-A)") (class "Default")
      (node (ref "D20") (pin "1") (pinfunction "A_1") (pintype "passive"))
      (node (ref "R49") (pin "1") (pinfunction "1_1") (pintype "passive"))
    )
    (net (code "26") (name "Net-(D21-A)") (class "Default")
      (node (ref "D21") (pin "1") (pinfunction "A_1") (pintype "passive"))
      (node (ref "R50") (pin "1") (pinfunction "1_1") (pintype "passive"))
    )
    (net (code "27") (name "Net-(Q1-DRAIN)") (class "Default")
      (node (ref "F1") (pin "2") (pinfunction "2_2") (pintype "passive"))
      (node (ref "Q1") (pin "2") (pinfunction "DRAIN_2") (pintype "passive"))
    )
    (net (code "28") (name "Net-(Q1-GATE)") (class "Default")
      (node (ref "Q1") (pin "1") (pinfunction "GATE_1") (pintype "passive"))
      (node (ref "R5") (pin "2") (pinfunction "2_2") (pintype "passive"))
    )
    (net (code "29") (name "Net-(Q5-DRAIN)") (class "Default")
      (node (ref "F2") (pin "2") (pinfunction "2_2") (pintype "passive"))
      (node (ref "Q5") (pin "2") (pinfunction "DRAIN_2") (pintype "passive"))
    )
    (net (code "30") (name "Net-(Q5-GATE)") (class "Default")
      (node (ref "Q5") (pin "1") (pinfunction "GATE_1") (pintype "passive"))
      (node (ref "R96") (pin "2") (pinfunction "2_2") (pintype "passive"))
    )
    (net (code "31") (name "Net-(Q7-DRAIN)") (class "Default")
      (node (ref "F3") (pin "2") (pinfunction "2_2") (pintype "passive"))
      (node (ref "Q7") (pin "2") (pinfunction "DRAIN_2") (pintype "passive"))
    )
    (net (code "32") (name "Net-(Q7-GATE)") (class "Default")
      (node (ref "Q7") (pin "1") (pinfunction "GATE_1") (pintype "passive"))
      (node (ref "R97") (pin "2") (pinfunction "2_2") (pintype "passive"))
    )
    (net (code "33") (name "Net-(U5-BOOT)") (class "Default")
      (node (ref "C3") (pin "2") (pinfunction "2_2") (pintype "passive"))
      (node (ref "U5") (pin "1") (pinfunction "BOOT_1") (pintype "passive"))
    )
    (net (code "34") (name "Net-(U5-COMP)") (class "Default")
      (node (ref "C67") (pin "2") (pinfunction "2_2") (pintype "passive"))
      (node (ref "R6") (pin "2") (pinfunction "2_2") (pintype "passive"))
      (node (ref "U5") (pin "6") (pinfunction "COMP_6") (pintype "passive"))
    )
    (net (code "35") (name "Net-(U5-EN)") (class "Default")
      (node (ref "R1") (pin "1") (pinfunction "1_1") (pintype "passive"))
      (node (ref "R4") (pin "2") (pinfunction "2_2") (pintype "passive"))
      (node (ref "U5") (pin "3") (pinfunction "EN_3") (pintype "input"))
    )
    (net (code "36") (name "Net-(U5-SS)") (class "Default")
      (node (ref "C68") (pin "1") (pinfunction "1_1") (pintype "passive"))
      (node (ref "U5") (pin "4") (pinfunction "SS_4") (pintype "input"))
    )
    (net (code "37") (name "Net-(U5-VSENSE)") (class "Default")
      (node (ref "R3") (pin "1") (pinfunction "1_1") (pintype "passive"))
      (node (ref "R7") (pin "2") (pinfunction "2_2") (pintype "passive"))
      (node (ref "U5") (pin "5") (pinfunction "VSENSE_5") (pintype "input"))
    )
  )
)
